# criticality_shield.net
KiCad netlist of a schematic drawn in EAGLE
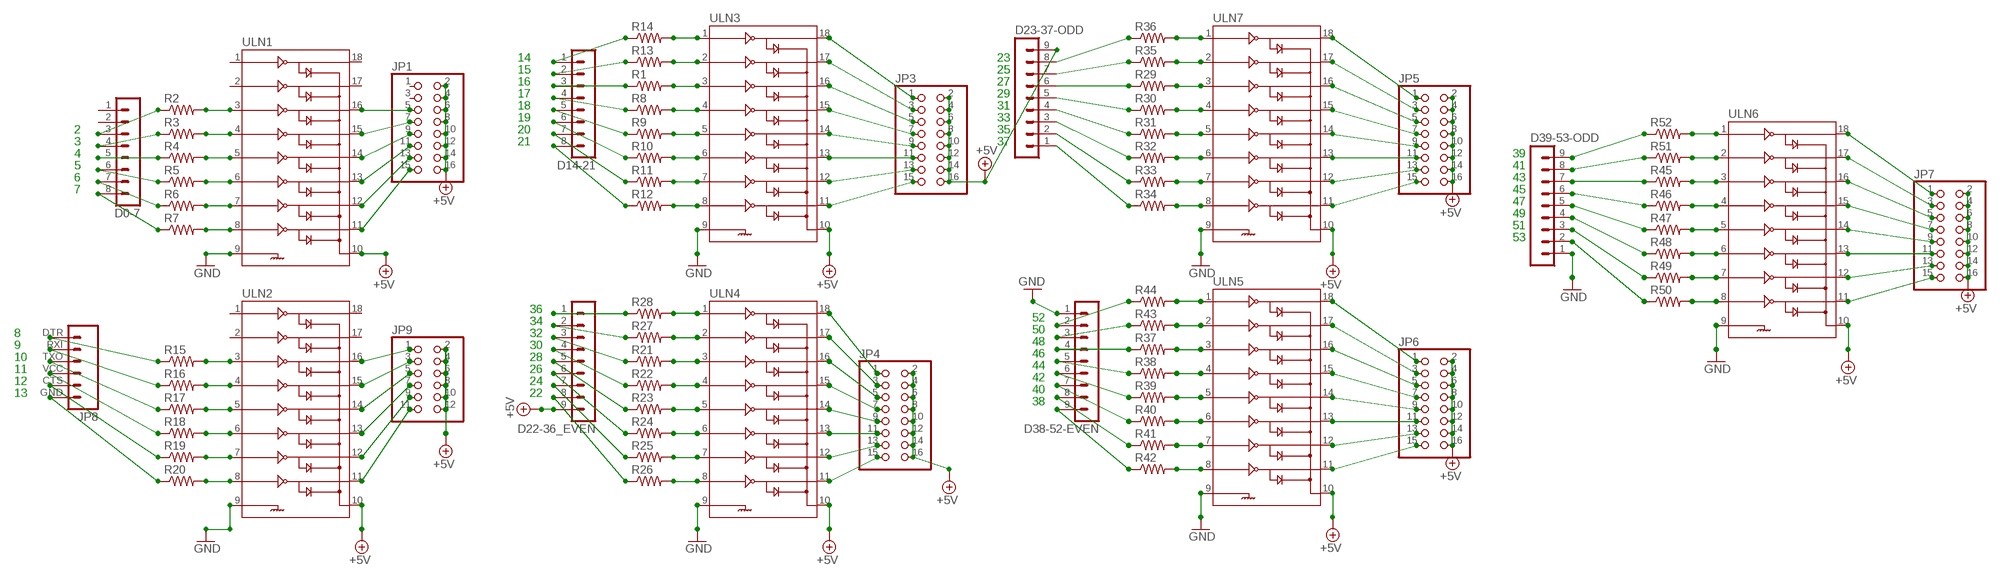
[diagram p0: schematic, sheet 1]

(export (version "E")
  (design (tool "Eeschema 10.0.6"))
  (components
    (comp (ref "D0-7")
      (value "MA08-1")
      (footprint "eagle-import:MA08-1")
      (libsource (lib "eagle-import") (part "MA08-1"))
    )
    (comp (ref "D14-21")
      (value "MA08-1")
      (footprint "eagle-import:MA08-1")
      (libsource (lib "eagle-import") (part "MA08-1"))
    )
    (comp (ref "D22-36_EVEN")
      (value "MA09-1")
      (footprint "eagle-import:MA09-1")
      (libsource (lib "eagle-import") (part "MA09-1"))
    )
    (comp (ref "D23-37-ODD")
      (value "MA09-1")
      (footprint "eagle-import:MA09-1")
      (libsource (lib "eagle-import") (part "MA09-1"))
    )
    (comp (ref "D38-52-EVEN")
      (value "MA09-1")
      (footprint "eagle-import:MA09-1")
      (libsource (lib "eagle-import") (part "MA09-1"))
    )
    (comp (ref "D39-53-ODD")
      (value "MA09-1")
      (footprint "eagle-import:MA09-1")
      (libsource (lib "eagle-import") (part "MA09-1"))
    )
    (comp (ref "JP1")
      (value "PINHD-2X8")
      (footprint "eagle-import:2X08")
      (libsource (lib "eagle-import") (part "PINHD-2X8"))
    )
    (comp (ref "JP3")
      (value "PINHD-2X8")
      (footprint "eagle-import:2X08")
      (libsource (lib "eagle-import") (part "PINHD-2X8"))
    )
    (comp (ref "JP4")
      (value "PINHD-2X8")
      (footprint "eagle-import:2X08")
      (libsource (lib "eagle-import") (part "PINHD-2X8"))
    )
    (comp (ref "JP5")
      (value "PINHD-2X8")
      (footprint "eagle-import:2X08")
      (libsource (lib "eagle-import") (part "PINHD-2X8"))
    )
    (comp (ref "JP6")
      (value "PINHD-2X8")
      (footprint "eagle-import:2X08")
      (libsource (lib "eagle-import") (part "PINHD-2X8"))
    )
    (comp (ref "JP7")
      (value "PINHD-2X8")
      (footprint "eagle-import:2X08")
      (libsource (lib "eagle-import") (part "PINHD-2X8"))
    )
    (comp (ref "JP8")
      (value "M06SIP")
      (footprint "eagle-import:1X06")
      (libsource (lib "eagle-import") (part "M06SIP"))
    )
    (comp (ref "JP9")
      (value "PINHD-2X6")
      (footprint "eagle-import:2X06")
      (libsource (lib "eagle-import") (part "PINHD-2X6"))
    )
    (comp (ref "R1")
      (value "RESISTOR0603")
      (footprint "eagle-import:0603-RES")
      (libsource (lib "eagle-import") (part "RESISTOR0603"))
    )
    (comp (ref "R2")
      (value "RESISTOR0603")
      (footprint "eagle-import:0603-RES")
      (libsource (lib "eagle-import") (part "RESISTOR0603"))
    )
    (comp (ref "R3")
      (value "RESISTOR0603")
      (footprint "eagle-import:0603-RES")
      (libsource (lib "eagle-import") (part "RESISTOR0603"))
    )
    (comp (ref "R4")
      (value "RESISTOR0603")
      (footprint "eagle-import:0603-RES")
      (libsource (lib "eagle-import") (part "RESISTOR0603"))
    )
    (comp (ref "R5")
      (value "RESISTOR0603")
      (footprint "eagle-import:0603-RES")
      (libsource (lib "eagle-import") (part "RESISTOR0603"))
    )
    (comp (ref "R6")
      (value "RESISTOR0603")
      (footprint "eagle-import:0603-RES")
      (libsource (lib "eagle-import") (part "RESISTOR0603"))
    )
    (comp (ref "R7")
      (value "RESISTOR0603")
      (footprint "eagle-import:0603-RES")
      (libsource (lib "eagle-import") (part "RESISTOR0603"))
    )
    (comp (ref "R8")
      (value "RESISTOR0603")
      (footprint "eagle-import:0603-RES")
      (libsource (lib "eagle-import") (part "RESISTOR0603"))
    )
    (comp (ref "R9")
      (value "RESISTOR0603")
      (footprint "eagle-import:0603-RES")
      (libsource (lib "eagle-import") (part "RESISTOR0603"))
    )
    (comp (ref "R10")
      (value "RESISTOR0603")
      (footprint "eagle-import:0603-RES")
      (libsource (lib "eagle-import") (part "RESISTOR0603"))
    )
    (comp (ref "R11")
      (value "RESISTOR0603")
      (footprint "eagle-import:0603-RES")
      (libsource (lib "eagle-import") (part "RESISTOR0603"))
    )
    (comp (ref "R12")
      (value "RESISTOR0603")
      (footprint "eagle-import:0603-RES")
      (libsource (lib "eagle-import") (part "RESISTOR0603"))
    )
    (comp (ref "R13")
      (value "RESISTOR0603")
      (footprint "eagle-import:0603-RES")
      (libsource (lib "eagle-import") (part "RESISTOR0603"))
    )
    (comp (ref "R14")
      (value "RESISTOR0603")
      (footprint "eagle-import:0603-RES")
      (libsource (lib "eagle-import") (part "RESISTOR0603"))
    )
    (comp (ref "R15")
      (value "RESISTOR0603")
      (footprint "eagle-import:0603-RES")
      (libsource (lib "eagle-import") (part "RESISTOR0603"))
    )
    (comp (ref "R16")
      (value "RESISTOR0603")
      (footprint "eagle-import:0603-RES")
      (libsource (lib "eagle-import") (part "RESISTOR0603"))
    )
    (comp (ref "R17")
      (value "RESISTOR0603")
      (footprint "eagle-import:0603-RES")
      (libsource (lib "eagle-import") (part "RESISTOR0603"))
    )
    (comp (ref "R18")
      (value "RESISTOR0603")
      (footprint "eagle-import:0603-RES")
      (libsource (lib "eagle-import") (part "RESISTOR0603"))
    )
    (comp (ref "R19")
      (value "RESISTOR0603")
      (footprint "eagle-import:0603-RES")
      (libsource (lib "eagle-import") (part "RESISTOR0603"))
    )
    (comp (ref "R20")
      (value "RESISTOR0603")
      (footprint "eagle-import:0603-RES")
      (libsource (lib "eagle-import") (part "RESISTOR0603"))
    )
    (comp (ref "R21")
      (value "RESISTOR0603")
      (footprint "eagle-import:0603-RES")
      (libsource (lib "eagle-import") (part "RESISTOR0603"))
    )
    (comp (ref "R22")
      (value "RESISTOR0603")
      (footprint "eagle-import:0603-RES")
      (libsource (lib "eagle-import") (part "RESISTOR0603"))
    )
    (comp (ref "R23")
      (value "RESISTOR0603")
      (footprint "eagle-import:0603-RES")
      (libsource (lib "eagle-import") (part "RESISTOR0603"))
    )
    (comp (ref "R24")
      (value "RESISTOR0603")
      (footprint "eagle-import:0603-RES")
      (libsource (lib "eagle-import") (part "RESISTOR0603"))
    )
    (comp (ref "R25")
      (value "RESISTOR0603")
      (footprint "eagle-import:0603-RES")
      (libsource (lib "eagle-import") (part "RESISTOR0603"))
    )
    (comp (ref "R26")
      (value "RESISTOR0603")
      (footprint "eagle-import:0603-RES")
      (libsource (lib "eagle-import") (part "RESISTOR0603"))
    )
    (comp (ref "R27")
      (value "RESISTOR0603")
      (footprint "eagle-import:0603-RES")
      (libsource (lib "eagle-import") (part "RESISTOR0603"))
    )
    (comp (ref "R28")
      (value "RESISTOR0603")
      (footprint "eagle-import:0603-RES")
      (libsource (lib "eagle-import") (part "RESISTOR0603"))
    )
    (comp (ref "R29")
      (value "RESISTOR0603")
      (footprint "eagle-import:0603-RES")
      (libsource (lib "eagle-import") (part "RESISTOR0603"))
    )
    (comp (ref "R30")
      (value "RESISTOR0603")
      (footprint "eagle-import:0603-RES")
      (libsource (lib "eagle-import") (part "RESISTOR0603"))
    )
    (comp (ref "R31")
      (value "RESISTOR0603")
      (footprint "eagle-import:0603-RES")
      (libsource (lib "eagle-import") (part "RESISTOR0603"))
    )
    (comp (ref "R32")
      (value "RESISTOR0603")
      (footprint "eagle-import:0603-RES")
      (libsource (lib "eagle-import") (part "RESISTOR0603"))
    )
    (comp (ref "R33")
      (value "RESISTOR0603")
      (footprint "eagle-import:0603-RES")
      (libsource (lib "eagle-import") (part "RESISTOR0603"))
    )
    (comp (ref "R34")
      (value "RESISTOR0603")
      (footprint "eagle-import:0603-RES")
      (libsource (lib "eagle-import") (part "RESISTOR0603"))
    )
    (comp (ref "R35")
      (value "RESISTOR0603")
      (footprint "eagle-import:0603-RES")
      (libsource (lib "eagle-import") (part "RESISTOR0603"))
    )
    (comp (ref "R36")
      (value "RESISTOR0603")
      (footprint "eagle-import:0603-RES")
      (libsource (lib "eagle-import") (part "RESISTOR0603"))
    )
    (comp (ref "R37")
      (value "RESISTOR0603")
      (footprint "eagle-import:0603-RES")
      (libsource (lib "eagle-import") (part "RESISTOR0603"))
    )
    (comp (ref "R38")
      (value "RESISTOR0603")
      (footprint "eagle-import:0603-RES")
      (libsource (lib "eagle-import") (part "RESISTOR0603"))
    )
    (comp (ref "R39")
      (value "RESISTOR0603")
      (footprint "eagle-import:0603-RES")
      (libsource (lib "eagle-import") (part "RESISTOR0603"))
    )
    (comp (ref "R40")
      (value "RESISTOR0603")
      (footprint "eagle-import:0603-RES")
      (libsource (lib "eagle-import") (part "RESISTOR0603"))
    )
    (comp (ref "R41")
      (value "RESISTOR0603")
      (footprint "eagle-import:0603-RES")
      (libsource (lib "eagle-import") (part "RESISTOR0603"))
    )
    (comp (ref "R42")
      (value "RESISTOR0603")
      (footprint "eagle-import:0603-RES")
      (libsource (lib "eagle-import") (part "RESISTOR0603"))
    )
    (comp (ref "R43")
      (value "RESISTOR0603")
      (footprint "eagle-import:0603-RES")
      (libsource (lib "eagle-import") (part "RESISTOR0603"))
    )
    (comp (ref "R44")
      (value "RESISTOR0603")
      (footprint "eagle-import:0603-RES")
      (libsource (lib "eagle-import") (part "RESISTOR0603"))
    )
    (comp (ref "R45")
      (value "RESISTOR0603")
      (footprint "eagle-import:0603-RES")
      (libsource (lib "eagle-import") (part "RESISTOR0603"))
    )
    (comp (ref "R46")
      (value "RESISTOR0603")
      (footprint "eagle-import:0603-RES")
      (libsource (lib "eagle-import") (part "RESISTOR0603"))
    )
    (comp (ref "R47")
      (value "RESISTOR0603")
      (footprint "eagle-import:0603-RES")
      (libsource (lib "eagle-import") (part "RESISTOR0603"))
    )
    (comp (ref "R48")
      (value "RESISTOR0603")
      (footprint "eagle-import:0603-RES")
      (libsource (lib "eagle-import") (part "RESISTOR0603"))
    )
    (comp (ref "R49")
      (value "RESISTOR0603")
      (footprint "eagle-import:0603-RES")
      (libsource (lib "eagle-import") (part "RESISTOR0603"))
    )
    (comp (ref "R50")
      (value "RESISTOR0603")
      (footprint "eagle-import:0603-RES")
      (libsource (lib "eagle-import") (part "RESISTOR0603"))
    )
    (comp (ref "R51")
      (value "RESISTOR0603")
      (footprint "eagle-import:0603-RES")
      (libsource (lib "eagle-import") (part "RESISTOR0603"))
    )
    (comp (ref "R52")
      (value "RESISTOR0603")
      (footprint "eagle-import:0603-RES")
      (libsource (lib "eagle-import") (part "RESISTOR0603"))
    )
    (comp (ref "ULN1")
      (value "ULN2803SOICW")
      (footprint "eagle-import:SO18L")
      (libsource (lib "eagle-import") (part "ULN2803SOICW"))
    )
    (comp (ref "ULN2")
      (value "ULN2803SOICW")
      (footprint "eagle-import:SO18L")
      (libsource (lib "eagle-import") (part "ULN2803SOICW"))
    )
    (comp (ref "ULN3")
      (value "ULN2803SOICW")
      (footprint "eagle-import:SO18L")
      (libsource (lib "eagle-import") (part "ULN2803SOICW"))
    )
    (comp (ref "ULN4")
      (value "ULN2803SOICW")
      (footprint "eagle-import:SO18L")
      (libsource (lib "eagle-import") (part "ULN2803SOICW"))
    )
    (comp (ref "ULN5")
      (value "ULN2803SOICW")
      (footprint "eagle-import:SO18L")
      (libsource (lib "eagle-import") (part "ULN2803SOICW"))
    )
    (comp (ref "ULN6")
      (value "ULN2803SOICW")
      (footprint "eagle-import:SO18L")
      (libsource (lib "eagle-import") (part "ULN2803SOICW"))
    )
    (comp (ref "ULN7")
      (value "ULN2803SOICW")
      (footprint "eagle-import:SO18L")
      (libsource (lib "eagle-import") (part "ULN2803SOICW"))
    )
  )
  (nets
    (net (code "1") (name "+5V") (class "Default")
      (node (ref "D22-36_EVEN") (pin "9") (pinfunction "9_9") (pintype "passive"))
      (node (ref "D23-37-ODD") (pin "9") (pinfunction "9_9") (pintype "passive"))
      (node (ref "JP1") (pin "10") (pinfunction "10_10") (pintype "passive"))
      (node (ref "JP1") (pin "12") (pinfunction "12_12") (pintype "passive"))
      (node (ref "JP1") (pin "14") (pinfunction "14_14") (pintype "passive"))
      (node (ref "JP1") (pin "16") (pinfunction "16_16") (pintype "passive"))
      (node (ref "JP1") (pin "2") (pinfunction "2_2") (pintype "passive"))
      (node (ref "JP1") (pin "4") (pinfunction "4_4") (pintype "passive"))
      (node (ref "JP1") (pin "6") (pinfunction "6_6") (pintype "passive"))
      (node (ref "JP1") (pin "8") (pinfunction "8_8") (pintype "passive"))
      (node (ref "JP3") (pin "10") (pinfunction "10_10") (pintype "passive"))
      (node (ref "JP3") (pin "12") (pinfunction "12_12") (pintype "passive"))
      (node (ref "JP3") (pin "14") (pinfunction "14_14") (pintype "passive"))
      (node (ref "JP3") (pin "16") (pinfunction "16_16") (pintype "passive"))
      (node (ref "JP3") (pin "2") (pinfunction "2_2") (pintype "passive"))
      (node (ref "JP3") (pin "4") (pinfunction "4_4") (pintype "passive"))
      (node (ref "JP3") (pin "6") (pinfunction "6_6") (pintype "passive"))
      (node (ref "JP3") (pin "8") (pinfunction "8_8") (pintype "passive"))
      (node (ref "JP4") (pin "10") (pinfunction "10_10") (pintype "passive"))
      (node (ref "JP4") (pin "12") (pinfunction "12_12") (pintype "passive"))
      (node (ref "JP4") (pin "14") (pinfunction "14_14") (pintype "passive"))
      (node (ref "JP4") (pin "16") (pinfunction "16_16") (pintype "passive"))
      (node (ref "JP4") (pin "2") (pinfunction "2_2") (pintype "passive"))
      (node (ref "JP4") (pin "4") (pinfunction "4_4") (pintype "passive"))
      (node (ref "JP4") (pin "6") (pinfunction "6_6") (pintype "passive"))
      (node (ref "JP4") (pin "8") (pinfunction "8_8") (pintype "passive"))
      (node (ref "JP5") (pin "10") (pinfunction "10_10") (pintype "passive"))
      (node (ref "JP5") (pin "12") (pinfunction "12_12") (pintype "passive"))
      (node (ref "JP5") (pin "14") (pinfunction "14_14") (pintype "passive"))
      (node (ref "JP5") (pin "16") (pinfunction "16_16") (pintype "passive"))
      (node (ref "JP5") (pin "2") (pinfunction "2_2") (pintype "passive"))
      (node (ref "JP5") (pin "4") (pinfunction "4_4") (pintype "passive"))
      (node (ref "JP5") (pin "6") (pinfunction "6_6") (pintype "passive"))
      (node (ref "JP5") (pin "8") (pinfunction "8_8") (pintype "passive"))
      (node (ref "JP6") (pin "10") (pinfunction "10_10") (pintype "passive"))
      (node (ref "JP6") (pin "12") (pinfunction "12_12") (pintype "passive"))
      (node (ref "JP6") (pin "14") (pinfunction "14_14") (pintype "passive"))
      (node (ref "JP6") (pin "16") (pinfunction "16_16") (pintype "passive"))
      (node (ref "JP6") (pin "2") (pinfunction "2_2") (pintype "passive"))
      (node (ref "JP6") (pin "4") (pinfunction "4_4") (pintype "passive"))
      (node (ref "JP6") (pin "6") (pinfunction "6_6") (pintype "passive"))
      (node (ref "JP6") (pin "8") (pinfunction "8_8") (pintype "passive"))
      (node (ref "JP7") (pin "10") (pinfunction "10_10") (pintype "passive"))
      (node (ref "JP7") (pin "12") (pinfunction "12_12") (pintype "passive"))
      (node (ref "JP7") (pin "14") (pinfunction "14_14") (pintype "passive"))
      (node (ref "JP7") (pin "16") (pinfunction "16_16") (pintype "passive"))
      (node (ref "JP7") (pin "2") (pinfunction "2_2") (pintype "passive"))
      (node (ref "JP7") (pin "4") (pinfunction "4_4") (pintype "passive"))
      (node (ref "JP7") (pin "6") (pinfunction "6_6") (pintype "passive"))
      (node (ref "JP7") (pin "8") (pinfunction "8_8") (pintype "passive"))
      (node (ref "JP9") (pin "10") (pinfunction "10_10") (pintype "passive"))
      (node (ref "JP9") (pin "12") (pinfunction "12_12") (pintype "passive"))
      (node (ref "JP9") (pin "2") (pinfunction "2_2") (pintype "passive"))
      (node (ref "JP9") (pin "4") (pinfunction "4_4") (pintype "passive"))
      (node (ref "JP9") (pin "6") (pinfunction "6_6") (pintype "passive"))
      (node (ref "JP9") (pin "8") (pinfunction "8_8") (pintype "passive"))
      (node (ref "ULN1") (pin "10") (pinfunction "10_10") (pintype "bidirectional"))
      (node (ref "ULN2") (pin "10") (pinfunction "10_10") (pintype "bidirectional"))
      (node (ref "ULN3") (pin "10") (pinfunction "10_10") (pintype "bidirectional"))
      (node (ref "ULN4") (pin "10") (pinfunction "10_10") (pintype "bidirectional"))
      (node (ref "ULN5") (pin "10") (pinfunction "10_10") (pintype "bidirectional"))
      (node (ref "ULN6") (pin "10") (pinfunction "10_10") (pintype "bidirectional"))
      (node (ref "ULN7") (pin "10") (pinfunction "10_10") (pintype "bidirectional"))
    )
    (net (code "2") (name "GND") (class "Default")
      (node (ref "D38-52-EVEN") (pin "1") (pinfunction "1_1") (pintype "passive"))
      (node (ref "D39-53-ODD") (pin "1") (pinfunction "1_1") (pintype "passive"))
      (node (ref "ULN1") (pin "9") (pinfunction "9_9") (pintype "bidirectional"))
      (node (ref "ULN2") (pin "9") (pinfunction "9_9") (pintype "bidirectional"))
      (node (ref "ULN3") (pin "9") (pinfunction "9_9") (pintype "bidirectional"))
      (node (ref "ULN4") (pin "9") (pinfunction "9_9") (pintype "bidirectional"))
      (node (ref "ULN5") (pin "9") (pinfunction "9_9") (pintype "bidirectional"))
      (node (ref "ULN6") (pin "9") (pinfunction "9_9") (pintype "bidirectional"))
      (node (ref "ULN7") (pin "9") (pinfunction "9_9") (pintype "bidirectional"))
    )
    (net (code "3") (name "Net-(D0-7-Pad3)") (class "Default")
      (node (ref "D0-7") (pin "3") (pinfunction "3_3") (pintype "passive"))
      (node (ref "R2") (pin "1") (pinfunction "1_1") (pintype "passive"))
    )
    (net (code "4") (name "Net-(D0-7-Pad4)") (class "Default")
      (node (ref "D0-7") (pin "4") (pinfunction "4_4") (pintype "passive"))
      (node (ref "R3") (pin "1") (pinfunction "1_1") (pintype "passive"))
    )
    (net (code "5") (name "Net-(D0-7-Pad5)") (class "Default")
      (node (ref "D0-7") (pin "5") (pinfunction "5_5") (pintype "passive"))
      (node (ref "R4") (pin "1") (pinfunction "1_1") (pintype "passive"))
    )
    (net (code "6") (name "Net-(D0-7-Pad6)") (class "Default")
      (node (ref "D0-7") (pin "6") (pinfunction "6_6") (pintype "passive"))
      (node (ref "R5") (pin "1") (pinfunction "1_1") (pintype "passive"))
    )
    (net (code "7") (name "Net-(D0-7-Pad7)") (class "Default")
      (node (ref "D0-7") (pin "7") (pinfunction "7_7") (pintype "passive"))
      (node (ref "R6") (pin "1") (pinfunction "1_1") (pintype "passive"))
    )
    (net (code "8") (name "Net-(D0-7-Pad8)") (class "Default")
      (node (ref "D0-7") (pin "8") (pinfunction "8_8") (pintype "passive"))
      (node (ref "R7") (pin "1") (pinfunction "1_1") (pintype "passive"))
    )
    (net (code "9") (name "Net-(D14-21-Pad1)") (class "Default")
      (node (ref "D14-21") (pin "1") (pinfunction "1_1") (pintype "passive"))
      (node (ref "R14") (pin "1") (pinfunction "1_1") (pintype "passive"))
    )
    (net (code "10") (name "Net-(D14-21-Pad2)") (class "Default")
      (node (ref "D14-21") (pin "2") (pinfunction "2_2") (pintype "passive"))
      (node (ref "R13") (pin "1") (pinfunction "1_1") (pintype "passive"))
    )
    (net (code "11") (name "Net-(D14-21-Pad3)") (class "Default")
      (node (ref "D14-21") (pin "3") (pinfunction "3_3") (pintype "passive"))
      (node (ref "R1") (pin "1") (pinfunction "1_1") (pintype "passive"))
    )
    (net (code "12") (name "Net-(D14-21-Pad4)") (class "Default")
      (node (ref "D14-21") (pin "4") (pinfunction "4_4") (pintype "passive"))
      (node (ref "R8") (pin "1") (pinfunction "1_1") (pintype "passive"))
    )
    (net (code "13") (name "Net-(D14-21-Pad5)") (class "Default")
      (node (ref "D14-21") (pin "5") (pinfunction "5_5") (pintype "passive"))
      (node (ref "R9") (pin "1") (pinfunction "1_1") (pintype "passive"))
    )
    (net (code "14") (name "Net-(D14-21-Pad6)") (class "Default")
      (node (ref "D14-21") (pin "6") (pinfunction "6_6") (pintype "passive"))
      (node (ref "R10") (pin "1") (pinfunction "1_1") (pintype "passive"))
    )
    (net (code "15") (name "Net-(D14-21-Pad7)") (class "Default")
      (node (ref "D14-21") (pin "7") (pinfunction "7_7") (pintype "passive"))
      (node (ref "R11") (pin "1") (pinfunction "1_1") (pintype "passive"))
    )
    (net (code "16") (name "Net-(D14-21-Pad8)") (class "Default")
      (node (ref "D14-21") (pin "8") (pinfunction "8_8") (pintype "passive"))
      (node (ref "R12") (pin "1") (pinfunction "1_1") (pintype "passive"))
    )
    (net (code "17") (name "Net-(D22-36_EVEN-Pad1)") (class "Default")
      (node (ref "D22-36_EVEN") (pin "1") (pinfunction "1_1") (pintype "passive"))
      (node (ref "R28") (pin "1") (pinfunction "1_1") (pintype "passive"))
    )
    (net (code "18") (name "Net-(D22-36_EVEN-Pad2)") (class "Default")
      (node (ref "D22-36_EVEN") (pin "2") (pinfunction "2_2") (pintype "passive"))
      (node (ref "R27") (pin "1") (pinfunction "1_1") (pintype "passive"))
    )
    (net (code "19") (name "Net-(D22-36_EVEN-Pad3)") (class "Default")
      (node (ref "D22-36_EVEN") (pin "3") (pinfunction "3_3") (pintype "passive"))
      (node (ref "R21") (pin "1") (pinfunction "1_1") (pintype "passive"))
    )
    (net (code "20") (name "Net-(D22-36_EVEN-Pad4)") (class "Default")
      (node (ref "D22-36_EVEN") (pin "4") (pinfunction "4_4") (pintype "passive"))
      (node (ref "R22") (pin "1") (pinfunction "1_1") (pintype "passive"))
    )
    (net (code "21") (name "Net-(D22-36_EVEN-Pad5)") (class "Default")
      (node (ref "D22-36_EVEN") (pin "5") (pinfunction "5_5") (pintype "passive"))
      (node (ref "R23") (pin "1") (pinfunction "1_1") (pintype "passive"))
    )
    (net (code "22") (name "Net-(D22-36_EVEN-Pad6)") (class "Default")
      (node (ref "D22-36_EVEN") (pin "6") (pinfunction "6_6") (pintype "passive"))
      (node (ref "R24") (pin "1") (pinfunction "1_1") (pintype "passive"))
    )
    (net (code "23") (name "Net-(D22-36_EVEN-Pad7)") (class "Default")
      (node (ref "D22-36_EVEN") (pin "7") (pinfunction "7_7") (pintype "passive"))
      (node (ref "R25") (pin "1") (pinfunction "1_1") (pintype "passive"))
    )
    (net (code "24") (name "Net-(D22-36_EVEN-Pad8)") (class "Default")
      (node (ref "D22-36_EVEN") (pin "8") (pinfunction "8_8") (pintype "passive"))
      (node (ref "R26") (pin "1") (pinfunction "1_1") (pintype "passive"))
    )
    (net (code "25") (name "Net-(D23-37-ODD-Pad1)") (class "Default")
      (node (ref "D23-37-ODD") (pin "1") (pinfunction "1_1") (pintype "passive"))
      (node (ref "R34") (pin "1") (pinfunction "1_1") (pintype "passive"))
    )
    (net (code "26") (name "Net-(D23-37-ODD-Pad2)") (class "Default")
      (node (ref "D23-37-ODD") (pin "2") (pinfunction "2_2") (pintype "passive"))
      (node (ref "R33") (pin "1") (pinfunction "1_1") (pintype "passive"))
    )
    (net (code "27") (name "Net-(D23-37-ODD-Pad3)") (class "Default")
      (node (ref "D23-37-ODD") (pin "3") (pinfunction "3_3") (pintype "passive"))
      (node (ref "R32") (pin "1") (pinfunction "1_1") (pintype "passive"))
    )
    (net (code "28") (name "Net-(D23-37-ODD-Pad4)") (class "Default")
      (node (ref "D23-37-ODD") (pin "4") (pinfunction "4_4") (pintype "passive"))
      (node (ref "R31") (pin "1") (pinfunction "1_1") (pintype "passive"))
    )
    (net (code "29") (name "Net-(D23-37-ODD-Pad5)") (class "Default")
      (node (ref "D23-37-ODD") (pin "5") (pinfunction "5_5") (pintype "passive"))
      (node (ref "R30") (pin "1") (pinfunction "1_1") (pintype "passive"))
    )
    (net (code "30") (name "Net-(D23-37-ODD-Pad6)") (class "Default")
      (node (ref "D23-37-ODD") (pin "6") (pinfunction "6_6") (pintype "passive"))
      (node (ref "R29") (pin "1") (pinfunction "1_1") (pintype "passive"))
    )
    (net (code "31") (name "Net-(D23-37-ODD-Pad7)") (class "Default")
      (node (ref "D23-37-ODD") (pin "7") (pinfunction "7_7") (pintype "passive"))
      (node (ref "R35") (pin "1") (pinfunction "1_1") (pintype "passive"))
    )
    (net (code "32") (name "Net-(D23-37-ODD-Pad8)") (class "Default")
      (node (ref "D23-37-ODD") (pin "8") (pinfunction "8_8") (pintype "passive"))
      (node (ref "R36") (pin "1") (pinfunction "1_1") (pintype "passive"))
    )
    (net (code "33") (name "Net-(D38-52-EVEN-Pad2)") (class "Default")
      (node (ref "D38-52-EVEN") (pin "2") (pinfunction "2_2") (pintype "passive"))
      (node (ref "R44") (pin "1") (pinfunction "1_1") (pintype "passive"))
    )
    (net (code "34") (name "Net-(D38-52-EVEN-Pad3)") (class "Default")
      (node (ref "D38-52-EVEN") (pin "3") (pinfunction "3_3") (pintype "passive"))
      (node (ref "R43") (pin "1") (pinfunction "1_1") (pintype "passive"))
    )
    (net (code "35") (name "Net-(D38-52-EVEN-Pad4)") (class "Default")
      (node (ref "D38-52-EVEN") (pin "4") (pinfunction "4_4") (pintype "passive"))
      (node (ref "R37") (pin "1") (pinfunction "1_1") (pintype "passive"))
    )
    (net (code "36") (name "Net-(D38-52-EVEN-Pad5)") (class "Default")
      (node (ref "D38-52-EVEN") (pin "5") (pinfunction "5_5") (pintype "passive"))
      (node (ref "R38") (pin "1") (pinfunction "1_1") (pintype "passive"))
    )
    (net (code "37") (name "Net-(D38-52-EVEN-Pad6)") (class "Default")
      (node (ref "D38-52-EVEN") (pin "6") (pinfunction "6_6") (pintype "passive"))
      (node (ref "R39") (pin "1") (pinfunction "1_1") (pintype "passive"))
    )
    (net (code "38") (name "Net-(D38-52-EVEN-Pad7)") (class "Default")
      (node (ref "D38-52-EVEN") (pin "7") (pinfunction "7_7") (pintype "passive"))
      (node (ref "R40") (pin "1") (pinfunction "1_1") (pintype "passive"))
    )
    (net (code "39") (name "Net-(D38-52-EVEN-Pad8)") (class "Default")
      (node (ref "D38-52-EVEN") (pin "8") (pinfunction "8_8") (pintype "passive"))
      (node (ref "R41") (pin "1") (pinfunction "1_1") (pintype "passive"))
    )
    (net (code "40") (name "Net-(D38-52-EVEN-Pad9)") (class "Default")
      (node (ref "D38-52-EVEN") (pin "9") (pinfunction "9_9") (pintype "passive"))
      (node (ref "R42") (pin "1") (pinfunction "1_1") (pintype "passive"))
    )
    (net (code "41") (name "Net-(D39-53-ODD-Pad2)") (class "Default")
      (node (ref "D39-53-ODD") (pin "2") (pinfunction "2_2") (pintype "passive"))
      (node (ref "R50") (pin "1") (pinfunction "1_1") (pintype "passive"))
    )
    (net (code "42") (name "Net-(D39-53-ODD-Pad3)") (class "Default")
      (node (ref "D39-53-ODD") (pin "3") (pinfunction "3_3") (pintype "passive"))
      (node (ref "R49") (pin "1") (pinfunction "1_1") (pintype "passive"))
    )
    (net (code "43") (name "Net-(D39-53-ODD-Pad4)") (class "Default")
      (node (ref "D39-53-ODD") (pin "4") (pinfunction "4_4") (pintype "passive"))
      (node (ref "R48") (pin "1") (pinfunction "1_1") (pintype "passive"))
    )
    (net (code "44") (name "Net-(D39-53-ODD-Pad5)") (class "Default")
      (node (ref "D39-53-ODD") (pin "5") (pinfunction "5_5") (pintype "passive"))
      (node (ref "R47") (pin "1") (pinfunction "1_1") (pintype "passive"))
    )
    (net (code "45") (name "Net-(D39-53-ODD-Pad6)") (class "Default")
      (node (ref "D39-53-ODD") (pin "6") (pinfunction "6_6") (pintype "passive"))
      (node (ref "R46") (pin "1") (pinfunction "1_1") (pintype "passive"))
    )
    (net (code "46") (name "Net-(D39-53-ODD-Pad7)") (class "Default")
      (node (ref "D39-53-ODD") (pin "7") (pinfunction "7_7") (pintype "passive"))
      (node (ref "R45") (pin "1") (pinfunction "1_1") (pintype "passive"))
    )
    (net (code "47") (name "Net-(D39-53-ODD-Pad8)") (class "Default")
      (node (ref "D39-53-ODD") (pin "8") (pinfunction "8_8") (pintype "passive"))
      (node (ref "R51") (pin "1") (pinfunction "1_1") (pintype "passive"))
    )
    (net (code "48") (name "Net-(D39-53-ODD-Pad9)") (class "Default")
      (node (ref "D39-53-ODD") (pin "9") (pinfunction "9_9") (pintype "passive"))
      (node (ref "R52") (pin "1") (pinfunction "1_1") (pintype "passive"))
    )
    (net (code "49") (name "Net-(JP1-Pad5)") (class "Default")
      (node (ref "JP1") (pin "5") (pinfunction "5_5") (pintype "passive"))
      (node (ref "ULN1") (pin "16") (pinfunction "16_16") (pintype "bidirectional"))
    )
    (net (code "50") (name "Net-(JP1-Pad7)") (class "Default")
      (node (ref "JP1") (pin "7") (pinfunction "7_7") (pintype "passive"))
      (node (ref "ULN1") (pin "15") (pinfunction "15_15") (pintype "bidirectional"))
    )
    (net (code "51") (name "Net-(JP1-Pad9)") (class "Default")
      (node (ref "JP1") (pin "9") (pinfunction "9_9") (pintype "passive"))
      (node (ref "ULN1") (pin "14") (pinfunction "14_14") (pintype "bidirectional"))
    )
    (net (code "52") (name "Net-(JP1-Pad11)") (class "Default")
      (node (ref "JP1") (pin "11") (pinfunction "11_11") (pintype "passive"))
      (node (ref "ULN1") (pin "13") (pinfunction "13_13") (pintype "bidirectional"))
    )
    (net (code "53") (name "Net-(JP1-Pad13)") (class "Default")
      (node (ref "JP1") (pin "13") (pinfunction "13_13") (pintype "passive"))
      (node (ref "ULN1") (pin "12") (pinfunction "12_12") (pintype "bidirectional"))
    )
    (net (code "54") (name "Net-(JP1-Pad15)") (class "Default")
      (node (ref "JP1") (pin "15") (pinfunction "15_15") (pintype "passive"))
      (node (ref "ULN1") (pin "11") (pinfunction "11_11") (pintype "bidirectional"))
    )
    (net (code "55") (name "Net-(JP3-Pad1)") (class "Default")
      (node (ref "JP3") (pin "1") (pinfunction "1_1") (pintype "passive"))
      (node (ref "ULN3") (pin "18") (pinfunction "18_18") (pintype "bidirectional"))
    )
    (net (code "56") (name "Net-(JP3-Pad3)") (class "Default")
      (node (ref "JP3") (pin "3") (pinfunction "3_3") (pintype "passive"))
      (node (ref "ULN3") (pin "17") (pinfunction "17_17") (pintype "bidirectional"))
    )
    (net (code "57") (name "Net-(JP3-Pad5)") (class "Default")
      (node (ref "JP3") (pin "5") (pinfunction "5_5") (pintype "passive"))
      (node (ref "ULN3") (pin "16") (pinfunction "16_16") (pintype "bidirectional"))
    )
    (net (code "58") (name "Net-(JP3-Pad7)") (class "Default")
      (node (ref "JP3") (pin "7") (pinfunction "7_7") (pintype "passive"))
      (node (ref "ULN3") (pin "15") (pinfunction "15_15") (pintype "bidirectional"))
    )
    (net (code "59") (name "Net-(JP3-Pad9)") (class "Default")
      (node (ref "JP3") (pin "9") (pinfunction "9_9") (pintype "passive"))
      (node (ref "ULN3") (pin "14") (pinfunction "14_14") (pintype "bidirectional"))
    )
    (net (code "60") (name "Net-(JP3-Pad11)") (class "Default")
      (node (ref "JP3") (pin "11") (pinfunction "11_11") (pintype "passive"))
      (node (ref "ULN3") (pin "13") (pinfunction "13_13") (pintype "bidirectional"))
    )
    (net (code "61") (name "Net-(JP3-Pad13)") (class "Default")
      (node (ref "JP3") (pin "13") (pinfunction "13_13") (pintype "passive"))
      (node (ref "ULN3") (pin "12") (pinfunction "12_12") (pintype "bidirectional"))
    )
    (net (code "62") (name "Net-(JP3-Pad15)") (class "Default")
      (node (ref "JP3") (pin "15") (pinfunction "15_15") (pintype "passive"))
      (node (ref "ULN3") (pin "11") (pinfunction "11_11") (pintype "bidirectional"))
    )
    (net (code "63") (name "Net-(JP4-Pad1)") (class "Default")
      (node (ref "JP4") (pin "1") (pinfunction "1_1") (pintype "passive"))
      (node (ref "ULN4") (pin "18") (pinfunction "18_18") (pintype "bidirectional"))
    )
    (net (code "64") (name "Net-(JP4-Pad3)") (class "Default")
      (node (ref "JP4") (pin "3") (pinfunction "3_3") (pintype "passive"))
      (node (ref "ULN4") (pin "17") (pinfunction "17_17") (pintype "bidirectional"))
    )
    (net (code "65") (name "Net-(JP4-Pad5)") (class "Default")
      (node (ref "JP4") (pin "5") (pinfunction "5_5") (pintype "passive"))
      (node (ref "ULN4") (pin "16") (pinfunction "16_16") (pintype "bidirectional"))
    )
    (net (code "66") (name "Net-(JP4-Pad7)") (class "Default")
      (node (ref "JP4") (pin "7") (pinfunction "7_7") (pintype "passive"))
      (node (ref "ULN4") (pin "15") (pinfunction "15_15") (pintype "bidirectional"))
    )
    (net (code "67") (name "Net-(JP4-Pad9)") (class "Default")
      (node (ref "JP4") (pin "9") (pinfunction "9_9") (pintype "passive"))
      (node (ref "ULN4") (pin "14") (pinfunction "14_14") (pintype "bidirectional"))
    )
    (net (code "68") (name "Net-(JP4-Pad11)") (class "Default")
      (node (ref "JP4") (pin "11") (pinfunction "11_11") (pintype "passive"))
      (node (ref "ULN4") (pin "13") (pinfunction "13_13") (pintype "bidirectional"))
    )
    (net (code "69") (name "Net-(JP4-Pad13)") (class "Default")
      (node (ref "JP4") (pin "13") (pinfunction "13_13") (pintype "passive"))
      (node (ref "ULN4") (pin "12") (pinfunction "12_12") (pintype "bidirectional"))
    )
    (net (code "70") (name "Net-(JP4-Pad15)") (class "Default")
      (node (ref "JP4") (pin "15") (pinfunction "15_15") (pintype "passive"))
      (node (ref "ULN4") (pin "11") (pinfunction "11_11") (pintype "bidirectional"))
    )
    (net (code "71") (name "Net-(JP5-Pad1)") (class "Default")
      (node (ref "JP5") (pin "1") (pinfunction "1_1") (pintype "passive"))
      (node (ref "ULN7") (pin "18") (pinfunction "18_18") (pintype "bidirectional"))
    )
    (net (code "72") (name "Net-(JP5-Pad3)") (class "Default")
      (node (ref "JP5") (pin "3") (pinfunction "3_3") (pintype "passive"))
      (node (ref "ULN7") (pin "17") (pinfunction "17_17") (pintype "bidirectional"))
    )
    (net (code "73") (name "Net-(JP5-Pad5)") (class "Default")
      (node (ref "JP5") (pin "5") (pinfunction "5_5") (pintype "passive"))
      (node (ref "ULN7") (pin "16") (pinfunction "16_16") (pintype "bidirectional"))
    )
    (net (code "74") (name "Net-(JP5-Pad7)") (class "Default")
      (node (ref "JP5") (pin "7") (pinfunction "7_7") (pintype "passive"))
      (node (ref "ULN7") (pin "15") (pinfunction "15_15") (pintype "bidirectional"))
    )
    (net (code "75") (name "Net-(JP5-Pad9)") (class "Default")
      (node (ref "JP5") (pin "9") (pinfunction "9_9") (pintype "passive"))
      (node (ref "ULN7") (pin "14") (pinfunction "14_14") (pintype "bidirectional"))
    )
    (net (code "76") (name "Net-(JP5-Pad11)") (class "Default")
      (node (ref "JP5") (pin "11") (pinfunction "11_11") (pintype "passive"))
      (node (ref "ULN7") (pin "13") (pinfunction "13_13") (pintype "bidirectional"))
    )
    (net (code "77") (name "Net-(JP5-Pad13)") (class "Default")
      (node (ref "JP5") (pin "13") (pinfunction "13_13") (pintype "passive"))
      (node (ref "ULN7") (pin "12") (pinfunction "12_12") (pintype "bidirectional"))
    )
    (net (code "78") (name "Net-(JP5-Pad15)") (class "Default")
      (node (ref "JP5") (pin "15") (pinfunction "15_15") (pintype "passive"))
      (node (ref "ULN7") (pin "11") (pinfunction "11_11") (pintype "bidirectional"))
    )
    (net (code "79") (name "Net-(JP6-Pad1)") (class "Default")
      (node (ref "JP6") (pin "1") (pinfunction "1_1") (pintype "passive"))
      (node (ref "ULN5") (pin "18") (pinfunction "18_18") (pintype "bidirectional"))
    )
    (net (code "80") (name "Net-(JP6-Pad3)") (class "Default")
      (node (ref "JP6") (pin "3") (pinfunction "3_3") (pintype "passive"))
      (node (ref "ULN5") (pin "17") (pinfunction "17_17") (pintype "bidirectional"))
    )
    (net (code "81") (name "Net-(JP6-Pad5)") (class "Default")
      (node (ref "JP6") (pin "5") (pinfunction "5_5") (pintype "passive"))
      (node (ref "ULN5") (pin "16") (pinfunction "16_16") (pintype "bidirectional"))
    )
    (net (code "82") (name "Net-(JP6-Pad7)") (class "Default")
      (node (ref "JP6") (pin "7") (pinfunction "7_7") (pintype "passive"))
      (node (ref "ULN5") (pin "15") (pinfunction "15_15") (pintype "bidirectional"))
    )
    (net (code "83") (name "Net-(JP6-Pad9)") (class "Default")
      (node (ref "JP6") (pin "9") (pinfunction "9_9") (pintype "passive"))
      (node (ref "ULN5") (pin "14") (pinfunction "14_14") (pintype "bidirectional"))
    )
    (net (code "84") (name "Net-(JP6-Pad11)") (class "Default")
      (node (ref "JP6") (pin "11") (pinfunction "11_11") (pintype "passive"))
      (node (ref "ULN5") (pin "13") (pinfunction "13_13") (pintype "bidirectional"))
    )
    (net (code "85") (name "Net-(JP6-Pad13)") (class "Default")
      (node (ref "JP6") (pin "13") (pinfunction "13_13") (pintype "passive"))
      (node (ref "ULN5") (pin "12") (pinfunction "12_12") (pintype "bidirectional"))
    )
    (net (code "86") (name "Net-(JP6-Pad15)") (class "Default")
      (node (ref "JP6") (pin "15") (pinfunction "15_15") (pintype "passive"))
      (node (ref "ULN5") (pin "11") (pinfunction "11_11") (pintype "bidirectional"))
    )
    (net (code "87") (name "Net-(JP7-Pad1)") (class "Default")
      (node (ref "JP7") (pin "1") (pinfunction "1_1") (pintype "passive"))
      (node (ref "ULN6") (pin "18") (pinfunction "18_18") (pintype "bidirectional"))
    )
    (net (code "88") (name "Net-(JP7-Pad3)") (class "Default")
      (node (ref "JP7") (pin "3") (pinfunction "3_3") (pintype "passive"))
      (node (ref "ULN6") (pin "17") (pinfunction "17_17") (pintype "bidirectional"))
    )
    (net (code "89") (name "Net-(JP7-Pad5)") (class "Default")
      (node (ref "JP7") (pin "5") (pinfunction "5_5") (pintype "passive"))
      (node (ref "ULN6") (pin "16") (pinfunction "16_16") (pintype "bidirectional"))
    )
    (net (code "90") (name "Net-(JP7-Pad7)") (class "Default")
      (node (ref "JP7") (pin "7") (pinfunction "7_7") (pintype "passive"))
      (node (ref "ULN6") (pin "15") (pinfunction "15_15") (pintype "bidirectional"))
    )
    (net (code "91") (name "Net-(JP7-Pad9)") (class "Default")
      (node (ref "JP7") (pin "9") (pinfunction "9_9") (pintype "passive"))
      (node (ref "ULN6") (pin "14") (pinfunction "14_14") (pintype "bidirectional"))
    )
    (net (code "92") (name "Net-(JP7-Pad11)") (class "Default")
      (node (ref "JP7") (pin "11") (pinfunction "11_11") (pintype "passive"))
      (node (ref "ULN6") (pin "13") (pinfunction "13_13") (pintype "bidirectional"))
    )
    (net (code "93") (name "Net-(JP7-Pad13)") (class "Default")
      (node (ref "JP7") (pin "13") (pinfunction "13_13") (pintype "passive"))
      (node (ref "ULN6") (pin "12") (pinfunction "12_12") (pintype "bidirectional"))
    )
    (net (code "94") (name "Net-(JP7-Pad15)") (class "Default")
      (node (ref "JP7") (pin "15") (pinfunction "15_15") (pintype "passive"))
      (node (ref "ULN6") (pin "11") (pinfunction "11_11") (pintype "bidirectional"))
    )
    (net (code "95") (name "Net-(JP8-1)") (class "Default")
      (node (ref "JP8") (pin "DTR") (pinfunction "1_DTR") (pintype "passive"))
      (node (ref "R15") (pin "1") (pinfunction "1_1") (pintype "passive"))
    )
    (net (code "96") (name "Net-(JP8-2)") (class "Default")
      (node (ref "JP8") (pin "RXI") (pinfunction "2_RXI") (pintype "passive"))
      (node (ref "R16") (pin "1") (pinfunction "1_1") (pintype "passive"))
    )
    (net (code "97") (name "Net-(JP8-3)") (class "Default")
      (node (ref "JP8") (pin "TXO") (pinfunction "3_TXO") (pintype "passive"))
      (node (ref "R17") (pin "1") (pinfunction "1_1") (pintype "passive"))
    )
    (net (code "98") (name "Net-(JP8-4)") (class "Default")
      (node (ref "JP8") (pin "VCC") (pinfunction "4_VCC") (pintype "passive"))
      (node (ref "R18") (pin "1") (pinfunction "1_1") (pintype "passive"))
    )
    (net (code "99") (name "Net-(JP8-5)") (class "Default")
      (node (ref "JP8") (pin "CTS") (pinfunction "5_CTS") (pintype "passive"))
      (node (ref "R19") (pin "1") (pinfunction "1_1") (pintype "passive"))
    )
    (net (code "100") (name "Net-(JP8-6)") (class "Default")
      (node (ref "JP8") (pin "GND") (pinfunction "6_GND") (pintype "passive"))
      (node (ref "R20") (pin "1") (pinfunction "1_1") (pintype "passive"))
    )
    (net (code "101") (name "Net-(JP9-Pad1)") (class "Default")
      (node (ref "JP9") (pin "1") (pinfunction "1_1") (pintype "passive"))
      (node (ref "ULN2") (pin "16") (pinfunction "16_16") (pintype "bidirectional"))
    )
    (net (code "102") (name "Net-(JP9-Pad3)") (class "Default")
      (node (ref "JP9") (pin "3") (pinfunction "3_3") (pintype "passive"))
      (node (ref "ULN2") (pin "15") (pinfunction "15_15") (pintype "bidirectional"))
    )
    (net (code "103") (name "Net-(JP9-Pad5)") (class "Default")
      (node (ref "JP9") (pin "5") (pinfunction "5_5") (pintype "passive"))
      (node (ref "ULN2") (pin "14") (pinfunction "14_14") (pintype "bidirectional"))
    )
    (net (code "104") (name "Net-(JP9-Pad7)") (class "Default")
      (node (ref "JP9") (pin "7") (pinfunction "7_7") (pintype "passive"))
      (node (ref "ULN2") (pin "13") (pinfunction "13_13") (pintype "bidirectional"))
    )
    (net (code "105") (name "Net-(JP9-Pad9)") (class "Default")
      (node (ref "JP9") (pin "9") (pinfunction "9_9") (pintype "passive"))
      (node (ref "ULN2") (pin "12") (pinfunction "12_12") (pintype "bidirectional"))
    )
    (net (code "106") (name "Net-(JP9-Pad11)") (class "Default")
      (node (ref "JP9") (pin "11") (pinfunction "11_11") (pintype "passive"))
      (node (ref "ULN2") (pin "11") (pinfunction "11_11") (pintype "bidirectional"))
    )
    (net (code "107") (name "Net-(R1-Pad2)") (class "Default")
      (node (ref "R1") (pin "2") (pinfunction "2_2") (pintype "passive"))
      (node (ref "ULN3") (pin "3") (pinfunction "3_3") (pintype "bidirectional"))
    )
    (net (code "108") (name "Net-(R2-Pad2)") (class "Default")
      (node (ref "R2") (pin "2") (pinfunction "2_2") (pintype "passive"))
      (node (ref "ULN1") (pin "3") (pinfunction "3_3") (pintype "bidirectional"))
    )
    (net (code "109") (name "Net-(R3-Pad2)") (class "Default")
      (node (ref "R3") (pin "2") (pinfunction "2_2") (pintype "passive"))
      (node (ref "ULN1") (pin "4") (pinfunction "4_4") (pintype "bidirectional"))
    )
    (net (code "110") (name "Net-(R4-Pad2)") (class "Default")
      (node (ref "R4") (pin "2") (pinfunction "2_2") (pintype "passive"))
      (node (ref "ULN1") (pin "5") (pinfunction "5_5") (pintype "bidirectional"))
    )
    (net (code "111") (name "Net-(R5-Pad2)") (class "Default")
      (node (ref "R5") (pin "2") (pinfunction "2_2") (pintype "passive"))
      (node (ref "ULN1") (pin "6") (pinfunction "6_6") (pintype "bidirectional"))
    )
    (net (code "112") (name "Net-(R6-Pad2)") (class "Default")
      (node (ref "R6") (pin "2") (pinfunction "2_2") (pintype "passive"))
      (node (ref "ULN1") (pin "7") (pinfunction "7_7") (pintype "bidirectional"))
    )
    (net (code "113") (name "Net-(R7-Pad2)") (class "Default")
      (node (ref "R7") (pin "2") (pinfunction "2_2") (pintype "passive"))
      (node (ref "ULN1") (pin "8") (pinfunction "8_8") (pintype "bidirectional"))
    )
    (net (code "114") (name "Net-(R8-Pad2)") (class "Default")
      (node (ref "R8") (pin "2") (pinfunction "2_2") (pintype "passive"))
      (node (ref "ULN3") (pin "4") (pinfunction "4_4") (pintype "bidirectional"))
    )
    (net (code "115") (name "Net-(R9-Pad2)") (class "Default")
      (node (ref "R9") (pin "2") (pinfunction "2_2") (pintype "passive"))
      (node (ref "ULN3") (pin "5") (pinfunction "5_5") (pintype "bidirectional"))
    )
    (net (code "116") (name "Net-(R10-Pad2)") (class "Default")
      (node (ref "R10") (pin "2") (pinfunction "2_2") (pintype "passive"))
      (node (ref "ULN3") (pin "6") (pinfunction "6_6") (pintype "bidirectional"))
    )
    (net (code "117") (name "Net-(R11-Pad2)") (class "Default")
      (node (ref "R11") (pin "2") (pinfunction "2_2") (pintype "passive"))
      (node (ref "ULN3") (pin "7") (pinfunction "7_7") (pintype "bidirectional"))
    )
    (net (code "118") (name "Net-(R12-Pad2)") (class "Default")
      (node (ref "R12") (pin "2") (pinfunction "2_2") (pintype "passive"))
      (node (ref "ULN3") (pin "8") (pinfunction "8_8") (pintype "bidirectional"))
    )
    (net (code "119") (name "Net-(R13-Pad2)") (class "Default")
      (node (ref "R13") (pin "2") (pinfunction "2_2") (pintype "passive"))
      (node (ref "ULN3") (pin "2") (pinfunction "2_2") (pintype "bidirectional"))
    )
    (net (code "120") (name "Net-(R14-Pad2)") (class "Default")
      (node (ref "R14") (pin "2") (pinfunction "2_2") (pintype "passive"))
      (node (ref "ULN3") (pin "1") (pinfunction "1_1") (pintype "bidirectional"))
    )
    (net (code "121") (name "Net-(R15-Pad2)") (class "Default")
      (node (ref "R15") (pin "2") (pinfunction "2_2") (pintype "passive"))
      (node (ref "ULN2") (pin "3") (pinfunction "3_3") (pintype "bidirectional"))
    )
    (net (code "122") (name "Net-(R16-Pad2)") (class "Default")
      (node (ref "R16") (pin "2") (pinfunction "2_2") (pintype "passive"))
      (node (ref "ULN2") (pin "4") (pinfunction "4_4") (pintype "bidirectional"))
    )
    (net (code "123") (name "Net-(R17-Pad2)") (class "Default")
      (node (ref "R17") (pin "2") (pinfunction "2_2") (pintype "passive"))
      (node (ref "ULN2") (pin "5") (pinfunction "5_5") (pintype "bidirectional"))
    )
    (net (code "124") (name "Net-(R18-Pad2)") (class "Default")
      (node (ref "R18") (pin "2") (pinfunction "2_2") (pintype "passive"))
      (node (ref "ULN2") (pin "6") (pinfunction "6_6") (pintype "bidirectional"))
    )
    (net (code "125") (name "Net-(R19-Pad2)") (class "Default")
      (node (ref "R19") (pin "2") (pinfunction "2_2") (pintype "passive"))
      (node (ref "ULN2") (pin "7") (pinfunction "7_7") (pintype "bidirectional"))
    )
    (net (code "126") (name "Net-(R20-Pad2)") (class "Default")
      (node (ref "R20") (pin "2") (pinfunction "2_2") (pintype "passive"))
      (node (ref "ULN2") (pin "8") (pinfunction "8_8") (pintype "bidirectional"))
    )
    (net (code "127") (name "Net-(R21-Pad2)") (class "Default")
      (node (ref "R21") (pin "2") (pinfunction "2_2") (pintype "passive"))
      (node (ref "ULN4") (pin "3") (pinfunction "3_3") (pintype "bidirectional"))
    )
    (net (code "128") (name "Net-(R22-Pad2)") (class "Default")
      (node (ref "R22") (pin "2") (pinfunction "2_2") (pintype "passive"))
      (node (ref "ULN4") (pin "4") (pinfunction "4_4") (pintype "bidirectional"))
    )
    (net (code "129") (name "Net-(R23-Pad2)") (class "Default")
      (node (ref "R23") (pin "2") (pinfunction "2_2") (pintype "passive"))
      (node (ref "ULN4") (pin "5") (pinfunction "5_5") (pintype "bidirectional"))
    )
    (net (code "130") (name "Net-(R24-Pad2)") (class "Default")
      (node (ref "R24") (pin "2") (pinfunction "2_2") (pintype "passive"))
      (node (ref "ULN4") (pin "6") (pinfunction "6_6") (pintype "bidirectional"))
    )
    (net (code "131") (name "Net-(R25-Pad2)") (class "Default")
      (node (ref "R25") (pin "2") (pinfunction "2_2") (pintype "passive"))
      (node (ref "ULN4") (pin "7") (pinfunction "7_7") (pintype "bidirectional"))
    )
    (net (code "132") (name "Net-(R26-Pad2)") (class "Default")
      (node (ref "R26") (pin "2") (pinfunction "2_2") (pintype "passive"))
      (node (ref "ULN4") (pin "8") (pinfunction "8_8") (pintype "bidirectional"))
    )
    (net (code "133") (name "Net-(R27-Pad2)") (class "Default")
      (node (ref "R27") (pin "2") (pinfunction "2_2") (pintype "passive"))
      (node (ref "ULN4") (pin "2") (pinfunction "2_2") (pintype "bidirectional"))
    )
    (net (code "134") (name "Net-(R28-Pad2)") (class "Default")
      (node (ref "R28") (pin "2") (pinfunction "2_2") (pintype "passive"))
      (node (ref "ULN4") (pin "1") (pinfunction "1_1") (pintype "bidirectional"))
    )
    (net (code "135") (name "Net-(R29-Pad2)") (class "Default")
      (node (ref "R29") (pin "2") (pinfunction "2_2") (pintype "passive"))
      (node (ref "ULN7") (pin "3") (pinfunction "3_3") (pintype "bidirectional"))
    )
    (net (code "136") (name "Net-(R30-Pad2)") (class "Default")
      (node (ref "R30") (pin "2") (pinfunction "2_2") (pintype "passive"))
      (node (ref "ULN7") (pin "4") (pinfunction "4_4") (pintype "bidirectional"))
    )
    (net (code "137") (name "Net-(R31-Pad2)") (class "Default")
      (node (ref "R31") (pin "2") (pinfunction "2_2") (pintype "passive"))
      (node (ref "ULN7") (pin "5") (pinfunction "5_5") (pintype "bidirectional"))
    )
    (net (code "138") (name "Net-(R32-Pad2)") (class "Default")
      (node (ref "R32") (pin "2") (pinfunction "2_2") (pintype "passive"))
      (node (ref "ULN7") (pin "6") (pinfunction "6_6") (pintype "bidirectional"))
    )
    (net (code "139") (name "Net-(R33-Pad2)") (class "Default")
      (node (ref "R33") (pin "2") (pinfunction "2_2") (pintype "passive"))
      (node (ref "ULN7") (pin "7") (pinfunction "7_7") (pintype "bidirectional"))
    )
    (net (code "140") (name "Net-(R34-Pad2)") (class "Default")
      (node (ref "R34") (pin "2") (pinfunction "2_2") (pintype "passive"))
      (node (ref "ULN7") (pin "8") (pinfunction "8_8") (pintype "bidirectional"))
    )
    (net (code "141") (name "Net-(R35-Pad2)") (class "Default")
      (node (ref "R35") (pin "2") (pinfunction "2_2") (pintype "passive"))
      (node (ref "ULN7") (pin "2") (pinfunction "2_2") (pintype "bidirectional"))
    )
    (net (code "142") (name "Net-(R36-Pad2)") (class "Default")
      (node (ref "R36") (pin "2") (pinfunction "2_2") (pintype "passive"))
      (node (ref "ULN7") (pin "1") (pinfunction "1_1") (pintype "bidirectional"))
    )
    (net (code "143") (name "Net-(R37-Pad2)") (class "Default")
      (node (ref "R37") (pin "2") (pinfunction "2_2") (pintype "passive"))
      (node (ref "ULN5") (pin "3") (pinfunction "3_3") (pintype "bidirectional"))
    )
    (net (code "144") (name "Net-(R38-Pad2)") (class "Default")
      (node (ref "R38") (pin "2") (pinfunction "2_2") (pintype "passive"))
      (node (ref "ULN5") (pin "4") (pinfunction "4_4") (pintype "bidirectional"))
    )
    (net (code "145") (name "Net-(R39-Pad2)") (class "Default")
      (node (ref "R39") (pin "2") (pinfunction "2_2") (pintype "passive"))
      (node (ref "ULN5") (pin "5") (pinfunction "5_5") (pintype "bidirectional"))
    )
    (net (code "146") (name "Net-(R40-Pad2)") (class "Default")
      (node (ref "R40") (pin "2") (pinfunction "2_2") (pintype "passive"))
      (node (ref "ULN5") (pin "6") (pinfunction "6_6") (pintype "bidirectional"))
    )
    (net (code "147") (name "Net-(R41-Pad2)") (class "Default")
      (node (ref "R41") (pin "2") (pinfunction "2_2") (pintype "passive"))
      (node (ref "ULN5") (pin "7") (pinfunction "7_7") (pintype "bidirectional"))
    )
    (net (code "148") (name "Net-(R42-Pad2)") (class "Default")
      (node (ref "R42") (pin "2") (pinfunction "2_2") (pintype "passive"))
      (node (ref "ULN5") (pin "8") (pinfunction "8_8") (pintype "bidirectional"))
    )
    (net (code "149") (name "Net-(R43-Pad2)") (class "Default")
      (node (ref "R43") (pin "2") (pinfunction "2_2") (pintype "passive"))
      (node (ref "ULN5") (pin "2") (pinfunction "2_2") (pintype "bidirectional"))
    )
    (net (code "150") (name "Net-(R44-Pad2)") (class "Default")
      (node (ref "R44") (pin "2") (pinfunction "2_2") (pintype "passive"))
      (node (ref "ULN5") (pin "1") (pinfunction "1_1") (pintype "bidirectional"))
    )
    (net (code "151") (name "Net-(R45-Pad2)") (class "Default")
      (node (ref "R45") (pin "2") (pinfunction "2_2") (pintype "passive"))
      (node (ref "ULN6") (pin "3") (pinfunction "3_3") (pintype "bidirectional"))
    )
    (net (code "152") (name "Net-(R46-Pad2)") (class "Default")
      (node (ref "R46") (pin "2") (pinfunction "2_2") (pintype "passive"))
      (node (ref "ULN6") (pin "4") (pinfunction "4_4") (pintype "bidirectional"))
    )
    (net (code "153") (name "Net-(R47-Pad2)") (class "Default")
      (node (ref "R47") (pin "2") (pinfunction "2_2") (pintype "passive"))
      (node (ref "ULN6") (pin "5") (pinfunction "5_5") (pintype "bidirectional"))
    )
    (net (code "154") (name "Net-(R48-Pad2)") (class "Default")
      (node (ref "R48") (pin "2") (pinfunction "2_2") (pintype "passive"))
      (node (ref "ULN6") (pin "6") (pinfunction "6_6") (pintype "bidirectional"))
    )
    (net (code "155") (name "Net-(R49-Pad2)") (class "Default")
      (node (ref "R49") (pin "2") (pinfunction "2_2") (pintype "passive"))
      (node (ref "ULN6") (pin "7") (pinfunction "7_7") (pintype "bidirectional"))
    )
    (net (code "156") (name "Net-(R50-Pad2)") (class "Default")
      (node (ref "R50") (pin "2") (pinfunction "2_2") (pintype "passive"))
      (node (ref "ULN6") (pin "8") (pinfunction "8_8") (pintype "bidirectional"))
    )
    (net (code "157") (name "Net-(R51-Pad2)") (class "Default")
      (node (ref "R51") (pin "2") (pinfunction "2_2") (pintype "passive"))
      (node (ref "ULN6") (pin "2") (pinfunction "2_2") (pintype "bidirectional"))
    )
    (net (code "158") (name "Net-(R52-Pad2)") (class "Default")
      (node (ref "R52") (pin "2") (pinfunction "2_2") (pintype "passive"))
      (node (ref "ULN6") (pin "1") (pinfunction "1_1") (pintype "bidirectional"))
    )
    (net (code "159") (name "unconnected-(D0-7-Pad1)") (class "Default")
      (node (ref "D0-7") (pin "1") (pinfunction "1_1") (pintype "passive"))
    )
    (net (code "160") (name "unconnected-(D0-7-Pad2)") (class "Default")
      (node (ref "D0-7") (pin "2") (pinfunction "2_2") (pintype "passive"))
    )
    (net (code "161") (name "unconnected-(JP1-Pad1)") (class "Default")
      (node (ref "JP1") (pin "1") (pinfunction "1_1") (pintype "passive"))
    )
    (net (code "162") (name "unconnected-(JP1-Pad3)") (class "Default")
      (node (ref "JP1") (pin "3") (pinfunction "3_3") (pintype "passive"))
    )
    (net (code "163") (name "unconnected-(ULN1-Pad1)") (class "Default")
      (node (ref "ULN1") (pin "1") (pinfunction "1_1") (pintype "bidirectional"))
    )
    (net (code "164") (name "unconnected-(ULN1-Pad2)") (class "Default")
      (node (ref "ULN1") (pin "2") (pinfunction "2_2") (pintype "bidirectional"))
    )
    (net (code "165") (name "unconnected-(ULN1-Pad17)") (class "Default")
      (node (ref "ULN1") (pin "17") (pinfunction "17_17") (pintype "bidirectional"))
    )
    (net (code "166") (name "unconnected-(ULN1-Pad18)") (class "Default")
      (node (ref "ULN1") (pin "18") (pinfunction "18_18") (pintype "bidirectional"))
    )
    (net (code "167") (name "unconnected-(ULN2-Pad1)") (class "Default")
      (node (ref "ULN2") (pin "1") (pinfunction "1_1") (pintype "bidirectional"))
    )
    (net (code "168") (name "unconnected-(ULN2-Pad2)") (class "Default")
      (node (ref "ULN2") (pin "2") (pinfunction "2_2") (pintype "bidirectional"))
    )
    (net (code "169") (name "unconnected-(ULN2-Pad17)") (class "Default")
      (node (ref "ULN2") (pin "17") (pinfunction "17_17") (pintype "bidirectional"))
    )
    (net (code "170") (name "unconnected-(ULN2-Pad18)") (class "Default")
      (node (ref "ULN2") (pin "18") (pinfunction "18_18") (pintype "bidirectional"))
    )
  )
)
